# JSTCJ.net
KiCad netlist of a schematic drawn in Altium Designer
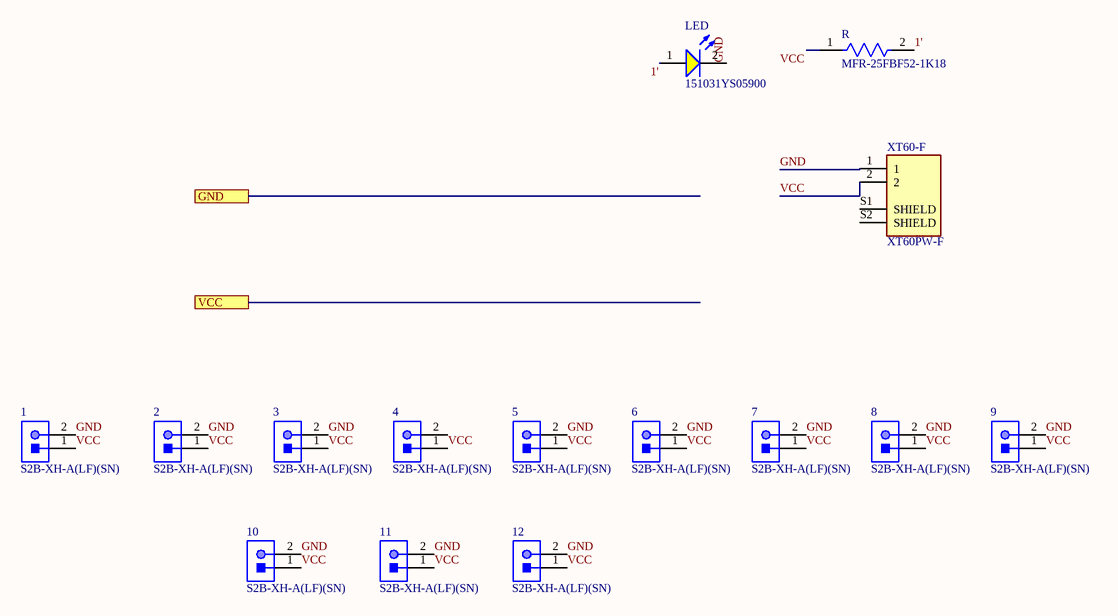
[diagram p0: JSTCJ.SchDoc]

(export (version "E")
  (design (tool "Eeschema 10.0.6"))
  (components
    (comp (ref "1")
      (value "S2B-XH-A(LF)(SN)")
      (footprint "JST-S2B-XH-A(LF)(SN)_V")
      (fields (field (name "MANUFACTURER") "JST"))
      (libsource (lib "APAC- Team Rudra-SRM Institute of Science and Technology") (part "CN-1P-M-R2"))
    )
    (comp (ref "2")
      (value "S2B-XH-A(LF)(SN)")
      (footprint "JST-S2B-XH-A(LF)(SN)_V")
      (fields (field (name "MANUFACTURER") "JST"))
      (libsource (lib "APAC- Team Rudra-SRM Institute of Science and Technology") (part "CN-1P-M-R2"))
    )
    (comp (ref "3")
      (value "S2B-XH-A(LF)(SN)")
      (footprint "JST-S2B-XH-A(LF)(SN)_V")
      (fields (field (name "MANUFACTURER") "JST"))
      (libsource (lib "APAC- Team Rudra-SRM Institute of Science and Technology") (part "CN-1P-M-R2"))
    )
    (comp (ref "4")
      (value "S2B-XH-A(LF)(SN)")
      (footprint "JST-S2B-XH-A(LF)(SN)_V")
      (fields (field (name "MANUFACTURER") "JST"))
      (libsource (lib "APAC- Team Rudra-SRM Institute of Science and Technology") (part "CN-1P-M-R2"))
    )
    (comp (ref "5")
      (value "S2B-XH-A(LF)(SN)")
      (footprint "JST-S2B-XH-A(LF)(SN)_V")
      (fields (field (name "MANUFACTURER") "JST"))
      (libsource (lib "APAC- Team Rudra-SRM Institute of Science and Technology") (part "CN-1P-M-R2"))
    )
    (comp (ref "6")
      (value "S2B-XH-A(LF)(SN)")
      (footprint "JST-S2B-XH-A(LF)(SN)_V")
      (fields (field (name "MANUFACTURER") "JST"))
      (libsource (lib "APAC- Team Rudra-SRM Institute of Science and Technology") (part "CN-1P-M-R2"))
    )
    (comp (ref "7")
      (value "S2B-XH-A(LF)(SN)")
      (footprint "JST-S2B-XH-A(LF)(SN)_V")
      (fields (field (name "MANUFACTURER") "JST"))
      (libsource (lib "APAC- Team Rudra-SRM Institute of Science and Technology") (part "CN-1P-M-R2"))
    )
    (comp (ref "8")
      (value "S2B-XH-A(LF)(SN)")
      (footprint "JST-S2B-XH-A(LF)(SN)_V")
      (fields (field (name "MANUFACTURER") "JST"))
      (libsource (lib "APAC- Team Rudra-SRM Institute of Science and Technology") (part "CN-1P-M-R2"))
    )
    (comp (ref "9")
      (value "S2B-XH-A(LF)(SN)")
      (footprint "JST-S2B-XH-A(LF)(SN)_V")
      (fields (field (name "MANUFACTURER") "JST"))
      (libsource (lib "APAC- Team Rudra-SRM Institute of Science and Technology") (part "CN-1P-M-R2"))
    )
    (comp (ref "10")
      (value "S2B-XH-A(LF)(SN)")
      (footprint "JST-S2B-XH-A(LF)(SN)_V")
      (fields (field (name "MANUFACTURER") "JST"))
      (libsource (lib "APAC- Team Rudra-SRM Institute of Science and Technology") (part "CN-1P-M-R2"))
    )
    (comp (ref "11")
      (value "S2B-XH-A(LF)(SN)")
      (footprint "JST-S2B-XH-A(LF)(SN)_V")
      (fields (field (name "MANUFACTURER") "JST"))
      (libsource (lib "APAC- Team Rudra-SRM Institute of Science and Technology") (part "CN-1P-M-R2"))
    )
    (comp (ref "12")
      (value "S2B-XH-A(LF)(SN)")
      (footprint "JST-S2B-XH-A(LF)(SN)_V")
      (fields (field (name "MANUFACTURER") "JST"))
      (libsource (lib "APAC- Team Rudra-SRM Institute of Science and Technology") (part "CN-1P-M-R2"))
    )
    (comp (ref "LED")
      (value "151031YS05900")
      (footprint "WL-TMRC_D3.95H5.3")
      (libsource (lib "Altium Content Vault") (part "LED_Yellow_1A-2K"))
    )
    (comp (ref "R")
      (value "MFR-25FBF52-1K18")
      (footprint "FP-MFR-25-MFG")
      (description "RES 1.18K OHM 1/4W 1% AXIAL")
      (fields (field (name "MANUFACTURER") "Yageo") (field (name "TOLERANCE") "1%"))
      (libsource (lib "Altium Content Vault") (part "1029c3af85768c4190bb7ad29bc67b5"))
    )
    (comp (ref "XT60-F")
      (value "XT60PW-F")
      (footprint "AMASS_XT60PW-F")
      (description "Socket DC Supply Connector Female")
      (fields (field (name "MF") "AMASS"))
      (libsource (lib "APAC- Team Rudra-SRM Institute of Science and Technology") (part "XT60PW-F"))
    )
  )
  (nets
    (net (code "1") (name "/1'") (class "Default")
      (node (ref "LED") (pin "1") (pinfunction "A_1") (pintype "passive"))
      (node (ref "R") (pin "2") (pinfunction "2_2") (pintype "passive"))
    )
    (net (code "2") (name "/GND") (class "Default")
      (node (ref "1") (pin "2") (pinfunction "2_2") (pintype "passive"))
      (node (ref "10") (pin "2") (pinfunction "2_2") (pintype "passive"))
      (node (ref "11") (pin "2") (pinfunction "2_2") (pintype "passive"))
      (node (ref "12") (pin "2") (pinfunction "2_2") (pintype "passive"))
      (node (ref "2") (pin "2") (pinfunction "2_2") (pintype "passive"))
      (node (ref "3") (pin "2") (pinfunction "2_2") (pintype "passive"))
      (node (ref "5") (pin "2") (pinfunction "2_2") (pintype "passive"))
      (node (ref "6") (pin "2") (pinfunction "2_2") (pintype "passive"))
      (node (ref "7") (pin "2") (pinfunction "2_2") (pintype "passive"))
      (node (ref "8") (pin "2") (pinfunction "2_2") (pintype "passive"))
      (node (ref "9") (pin "2") (pinfunction "2_2") (pintype "passive"))
      (node (ref "LED") (pin "2") (pinfunction "K_2") (pintype "passive"))
      (node (ref "XT60-F") (pin "1") (pinfunction "1_1") (pintype "passive"))
    )
    (net (code "3") (name "/VCC") (class "Default")
      (node (ref "1") (pin "1") (pinfunction "1_1") (pintype "passive"))
      (node (ref "10") (pin "1") (pinfunction "1_1") (pintype "passive"))
      (node (ref "11") (pin "1") (pinfunction "1_1") (pintype "passive"))
      (node (ref "12") (pin "1") (pinfunction "1_1") (pintype "passive"))
      (node (ref "2") (pin "1") (pinfunction "1_1") (pintype "passive"))
      (node (ref "3") (pin "1") (pinfunction "1_1") (pintype "passive"))
      (node (ref "4") (pin "1") (pinfunction "1_1") (pintype "passive"))
      (node (ref "5") (pin "1") (pinfunction "1_1") (pintype "passive"))
      (node (ref "6") (pin "1") (pinfunction "1_1") (pintype "passive"))
      (node (ref "7") (pin "1") (pinfunction "1_1") (pintype "passive"))
      (node (ref "8") (pin "1") (pinfunction "1_1") (pintype "passive"))
      (node (ref "9") (pin "1") (pinfunction "1_1") (pintype "passive"))
      (node (ref "R") (pin "1") (pinfunction "1_1") (pintype "passive"))
      (node (ref "XT60-F") (pin "2") (pinfunction "2_2") (pintype "passive"))
    )
    (net (code "4") (name "unconnected-(4-Pad2)") (class "Default")
      (node (ref "4") (pin "2") (pinfunction "2_2") (pintype "passive"))
    )
    (net (code "5") (name "unconnected-(XT60-F-SHIELD-PadS1)") (class "Default")
      (node (ref "XT60-F") (pin "S1") (pinfunction "SHIELD_S1") (pintype "passive"))
    )
    (net (code "6") (name "unconnected-(XT60-F-SHIELD-PadS2)") (class "Default")
      (node (ref "XT60-F") (pin "S2") (pinfunction "SHIELD_S2") (pintype "passive"))
    )
  )
)
